# bluz_battery_v1.net
KiCad netlist of a schematic drawn in EAGLE
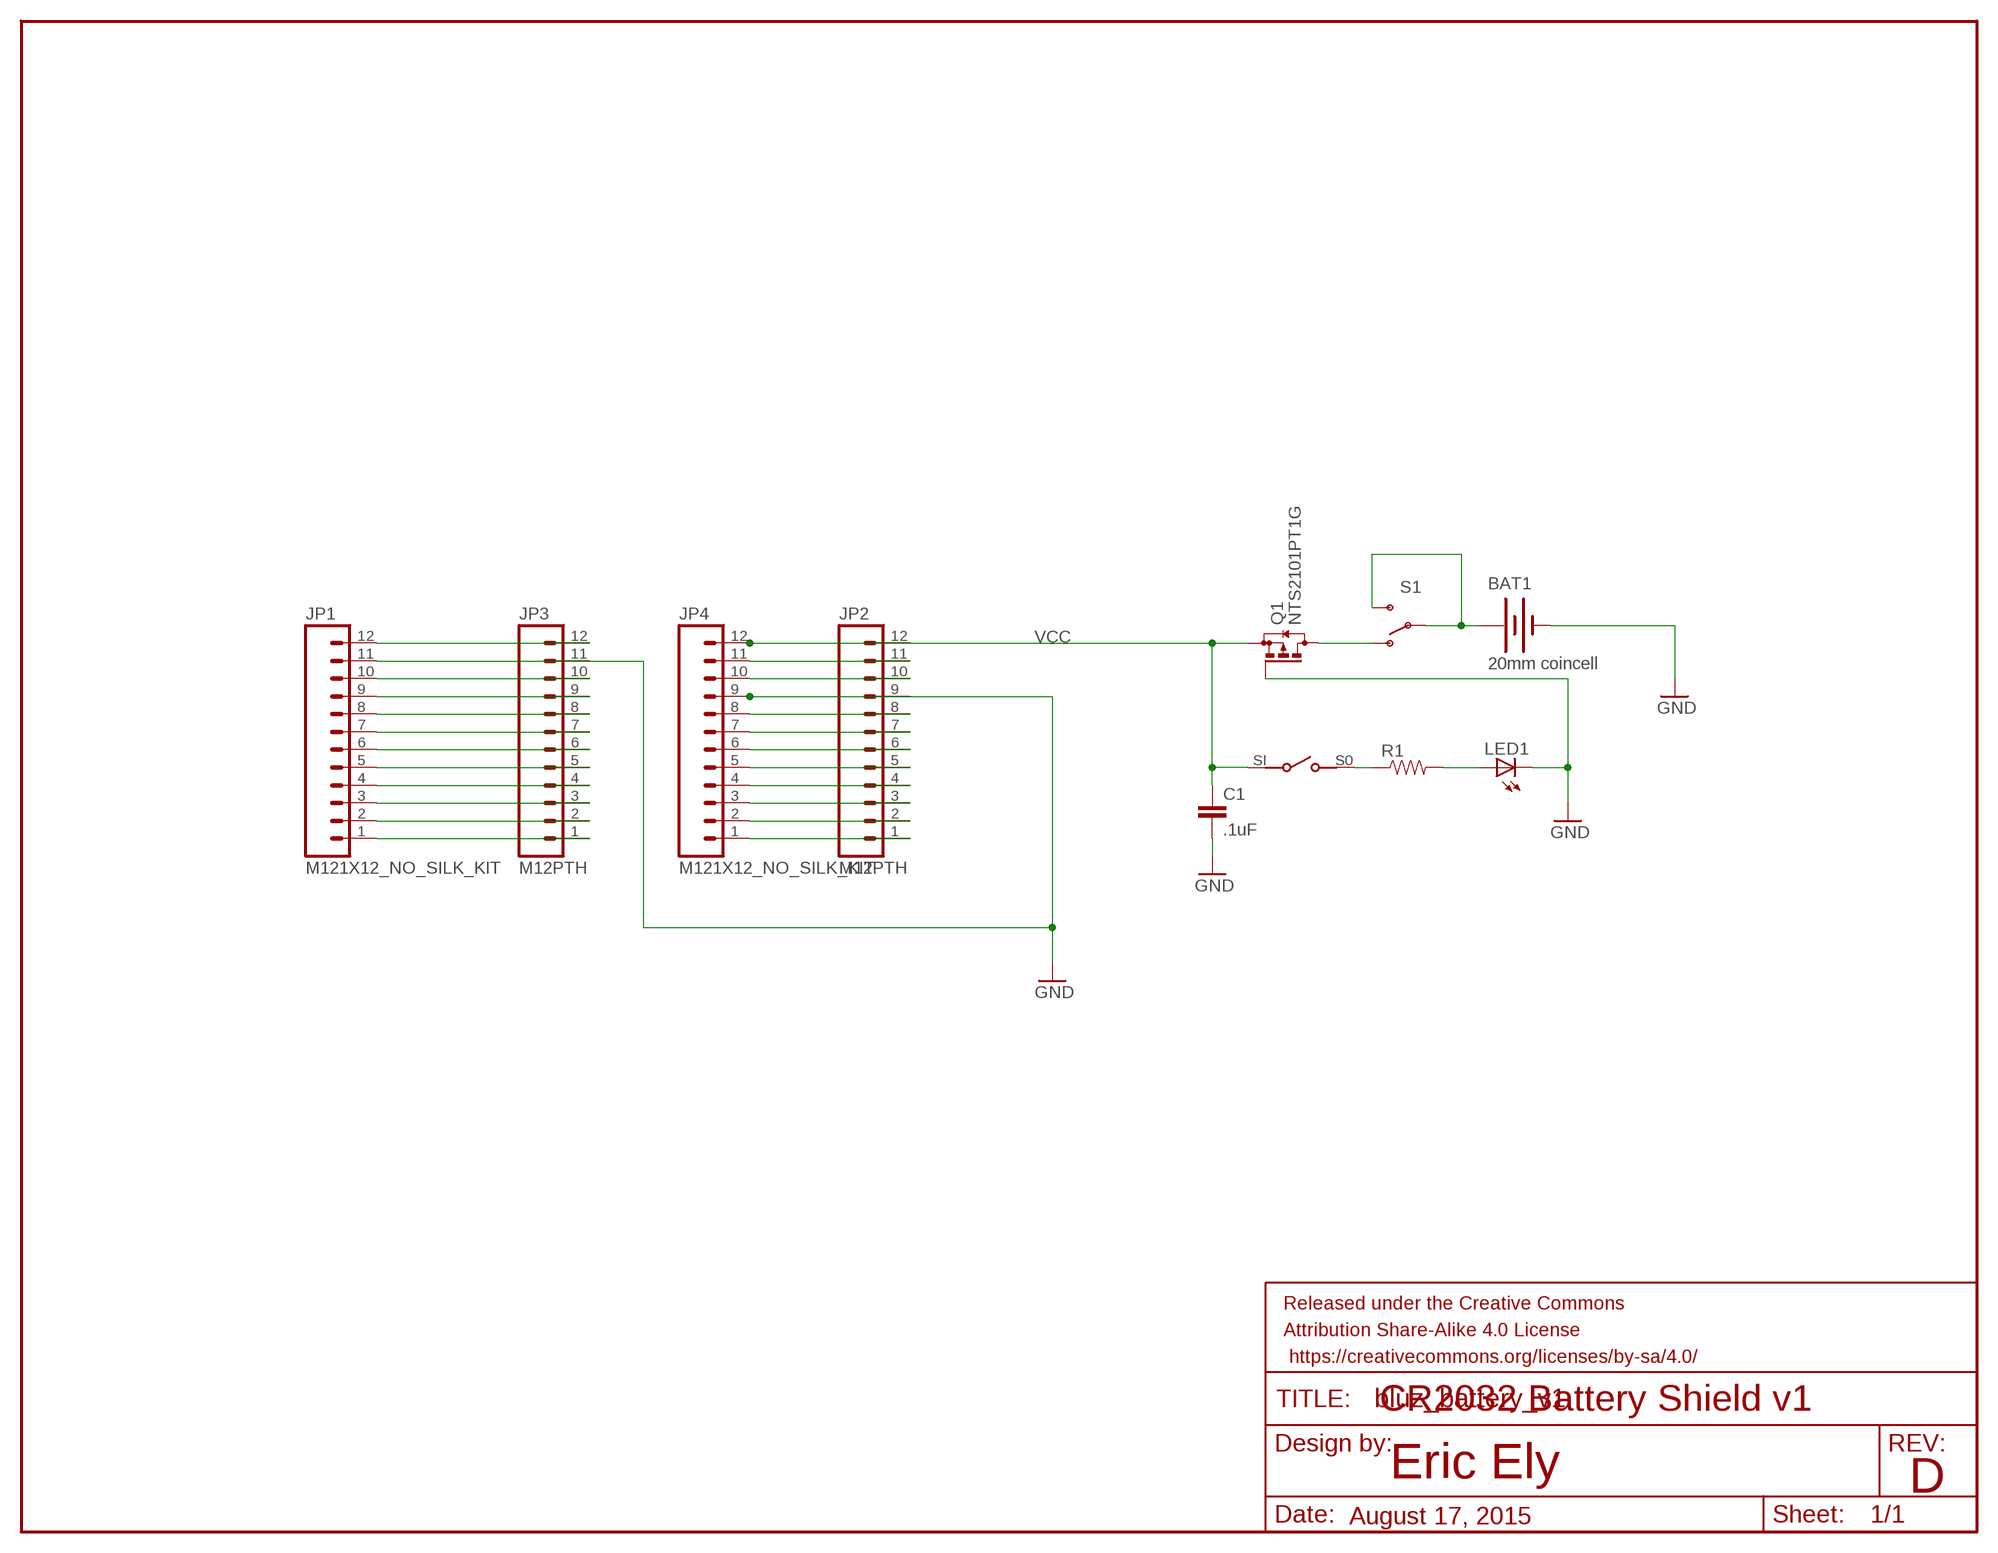
[diagram p0: schematic, sheet 1]

(export (version "E")
  (design (tool "Eeschema 10.0.6"))
  (components
    (comp (ref "BAT1")
      (value "20mm coincell")
      (footprint "eagle-import:BATTCON_20MM_4LEGS")
      (libsource (lib "eagle-import") (part "BATTERY20MM_4LEGS"))
    )
    (comp (ref "C1")
      (value ".1uF")
      (footprint "eagle-import:0603-CAP")
      (libsource (lib "eagle-import") (part "CAP0603-CAP"))
    )
    (comp (ref "FRAME1")
      (value "FRAME-LETTER")
      (footprint "eagle-import:CREATIVE_COMMONS")
      (libsource (lib "eagle-import") (part "FRAME-LETTER"))
    )
    (comp (ref "JP1")
      (value "M121X12_NO_SILK_KIT")
      (footprint "eagle-import:1X12_NO_SILK_KIT")
      (libsource (lib "eagle-import") (part "M121X12_NO_SILK_KIT"))
    )
    (comp (ref "JP2")
      (value "M12PTH")
      (footprint "eagle-import:1X12")
      (libsource (lib "eagle-import") (part "M12PTH"))
    )
    (comp (ref "JP3")
      (value "M12PTH")
      (footprint "eagle-import:1X12")
      (libsource (lib "eagle-import") (part "M12PTH"))
    )
    (comp (ref "JP4")
      (value "M121X12_NO_SILK_KIT")
      (footprint "eagle-import:1X12_NO_SILK_KIT")
      (libsource (lib "eagle-import") (part "M121X12_NO_SILK_KIT"))
    )
    (comp (ref "LED1")
      (value "LEDCHIPLED_0603")
      (footprint "eagle-import:CHIPLED_0603")
      (libsource (lib "eagle-import") (part "LEDCHIPLED_0603"))
    )
    (comp (ref "Q1")
      (value "NTS2101PT1G")
      (footprint "eagle-import:SOT323")
      (libsource (lib "eagle-import") (part "NTS2101PT1G"))
    )
    (comp (ref "R1")
      (value "RESISTOR0603-RES")
      (footprint "eagle-import:0603-RES")
      (libsource (lib "eagle-import") (part "RESISTOR0603-RES"))
    )
    (comp (ref "S1")
      (value "SWITCH-SPDTKIT")
      (footprint "eagle-import:SWITCH-SPDT_KIT")
      (libsource (lib "eagle-import") (part "SWITCH-SPDTKIT"))
    )
    (comp (ref "S2")
      (value "CHS-01TASMD")
      (footprint "eagle-import:CHS-01TA")
      (libsource (lib "eagle-import") (part "CHS-01TASMD"))
    )
  )
  (nets
    (net (code "1") (name "/VCC") (class "Default")
      (node (ref "C1") (pin "1") (pinfunction "1_1") (pintype "passive"))
      (node (ref "JP2") (pin "12") (pinfunction "12_12") (pintype "passive"))
      (node (ref "JP4") (pin "12") (pinfunction "12_12") (pintype "passive"))
      (node (ref "Q1") (pin "2") (pinfunction "S_2") (pintype "passive"))
      (node (ref "S2") (pin "SI") (pinfunction "S~{}_SI") (pintype "input"))
    )
    (net (code "2") (name "GND") (class "Default")
      (node (ref "BAT1") (pin "2") (pinfunction "-_2") (pintype "power_in"))
      (node (ref "C1") (pin "2") (pinfunction "2_2") (pintype "passive"))
      (node (ref "JP1") (pin "11") (pinfunction "11_11") (pintype "passive"))
      (node (ref "JP2") (pin "9") (pinfunction "9_9") (pintype "passive"))
      (node (ref "JP3") (pin "11") (pinfunction "11_11") (pintype "passive"))
      (node (ref "JP4") (pin "9") (pinfunction "9_9") (pintype "passive"))
      (node (ref "LED1") (pin "C") (pinfunction "C_C") (pintype "passive"))
      (node (ref "Q1") (pin "1") (pinfunction "G_1") (pintype "passive"))
    )
    (net (code "3") (name "Net-(BAT1-+)") (class "Default")
      (node (ref "BAT1") (pin "1") (pinfunction "+_1") (pintype "power_in"))
      (node (ref "S1") (pin "2") (pinfunction "P_2") (pintype "passive"))
      (node (ref "S1") (pin "3") (pinfunction "S_3") (pintype "passive"))
    )
    (net (code "4") (name "Net-(JP1-Pad1)") (class "Default")
      (node (ref "JP1") (pin "1") (pinfunction "1_1") (pintype "passive"))
      (node (ref "JP3") (pin "1") (pinfunction "1_1") (pintype "passive"))
    )
    (net (code "5") (name "Net-(JP1-Pad2)") (class "Default")
      (node (ref "JP1") (pin "2") (pinfunction "2_2") (pintype "passive"))
      (node (ref "JP3") (pin "2") (pinfunction "2_2") (pintype "passive"))
    )
    (net (code "6") (name "Net-(JP1-Pad3)") (class "Default")
      (node (ref "JP1") (pin "3") (pinfunction "3_3") (pintype "passive"))
      (node (ref "JP3") (pin "3") (pinfunction "3_3") (pintype "passive"))
    )
    (net (code "7") (name "Net-(JP1-Pad4)") (class "Default")
      (node (ref "JP1") (pin "4") (pinfunction "4_4") (pintype "passive"))
      (node (ref "JP3") (pin "4") (pinfunction "4_4") (pintype "passive"))
    )
    (net (code "8") (name "Net-(JP1-Pad5)") (class "Default")
      (node (ref "JP1") (pin "5") (pinfunction "5_5") (pintype "passive"))
      (node (ref "JP3") (pin "5") (pinfunction "5_5") (pintype "passive"))
    )
    (net (code "9") (name "Net-(JP1-Pad6)") (class "Default")
      (node (ref "JP1") (pin "6") (pinfunction "6_6") (pintype "passive"))
      (node (ref "JP3") (pin "6") (pinfunction "6_6") (pintype "passive"))
    )
    (net (code "10") (name "Net-(JP1-Pad7)") (class "Default")
      (node (ref "JP1") (pin "7") (pinfunction "7_7") (pintype "passive"))
      (node (ref "JP3") (pin "7") (pinfunction "7_7") (pintype "passive"))
    )
    (net (code "11") (name "Net-(JP1-Pad8)") (class "Default")
      (node (ref "JP1") (pin "8") (pinfunction "8_8") (pintype "passive"))
      (node (ref "JP3") (pin "8") (pinfunction "8_8") (pintype "passive"))
    )
    (net (code "12") (name "Net-(JP1-Pad9)") (class "Default")
      (node (ref "JP1") (pin "9") (pinfunction "9_9") (pintype "passive"))
      (node (ref "JP3") (pin "9") (pinfunction "9_9") (pintype "passive"))
    )
    (net (code "13") (name "Net-(JP1-Pad10)") (class "Default")
      (node (ref "JP1") (pin "10") (pinfunction "10_10") (pintype "passive"))
      (node (ref "JP3") (pin "10") (pinfunction "10_10") (pintype "passive"))
    )
    (net (code "14") (name "Net-(JP1-Pad12)") (class "Default")
      (node (ref "JP1") (pin "12") (pinfunction "12_12") (pintype "passive"))
      (node (ref "JP3") (pin "12") (pinfunction "12_12") (pintype "passive"))
    )
    (net (code "15") (name "Net-(JP2-Pad1)") (class "Default")
      (node (ref "JP2") (pin "1") (pinfunction "1_1") (pintype "passive"))
      (node (ref "JP4") (pin "1") (pinfunction "1_1") (pintype "passive"))
    )
    (net (code "16") (name "Net-(JP2-Pad2)") (class "Default")
      (node (ref "JP2") (pin "2") (pinfunction "2_2") (pintype "passive"))
      (node (ref "JP4") (pin "2") (pinfunction "2_2") (pintype "passive"))
    )
    (net (code "17") (name "Net-(JP2-Pad3)") (class "Default")
      (node (ref "JP2") (pin "3") (pinfunction "3_3") (pintype "passive"))
      (node (ref "JP4") (pin "3") (pinfunction "3_3") (pintype "passive"))
    )
    (net (code "18") (name "Net-(JP2-Pad4)") (class "Default")
      (node (ref "JP2") (pin "4") (pinfunction "4_4") (pintype "passive"))
      (node (ref "JP4") (pin "4") (pinfunction "4_4") (pintype "passive"))
    )
    (net (code "19") (name "Net-(JP2-Pad5)") (class "Default")
      (node (ref "JP2") (pin "5") (pinfunction "5_5") (pintype "passive"))
      (node (ref "JP4") (pin "5") (pinfunction "5_5") (pintype "passive"))
    )
    (net (code "20") (name "Net-(JP2-Pad6)") (class "Default")
      (node (ref "JP2") (pin "6") (pinfunction "6_6") (pintype "passive"))
      (node (ref "JP4") (pin "6") (pinfunction "6_6") (pintype "passive"))
    )
    (net (code "21") (name "Net-(JP2-Pad7)") (class "Default")
      (node (ref "JP2") (pin "7") (pinfunction "7_7") (pintype "passive"))
      (node (ref "JP4") (pin "7") (pinfunction "7_7") (pintype "passive"))
    )
    (net (code "22") (name "Net-(JP2-Pad8)") (class "Default")
      (node (ref "JP2") (pin "8") (pinfunction "8_8") (pintype "passive"))
      (node (ref "JP4") (pin "8") (pinfunction "8_8") (pintype "passive"))
    )
    (net (code "23") (name "Net-(JP2-Pad10)") (class "Default")
      (node (ref "JP2") (pin "10") (pinfunction "10_10") (pintype "passive"))
      (node (ref "JP4") (pin "10") (pinfunction "10_10") (pintype "passive"))
    )
    (net (code "24") (name "Net-(JP2-Pad11)") (class "Default")
      (node (ref "JP2") (pin "11") (pinfunction "11_11") (pintype "passive"))
      (node (ref "JP4") (pin "11") (pinfunction "11_11") (pintype "passive"))
    )
    (net (code "25") (name "Net-(LED1-PadA)") (class "Default")
      (node (ref "LED1") (pin "A") (pinfunction "A_A") (pintype "passive"))
      (node (ref "R1") (pin "2") (pinfunction "2_2") (pintype "passive"))
    )
    (net (code "26") (name "Net-(Q1-D)") (class "Default")
      (node (ref "Q1") (pin "3") (pinfunction "D_3") (pintype "passive"))
      (node (ref "S1") (pin "1") (pinfunction "O_1") (pintype "passive"))
    )
    (net (code "27") (name "Net-(S2-SO)") (class "Default")
      (node (ref "R1") (pin "1") (pinfunction "1_1") (pintype "passive"))
      (node (ref "S2") (pin "S0") (pinfunction "SO_S0") (pintype "output"))
    )
  )
)
